# LVDS_repeater.net
KiCad netlist of a schematic drawn in Altium Designer
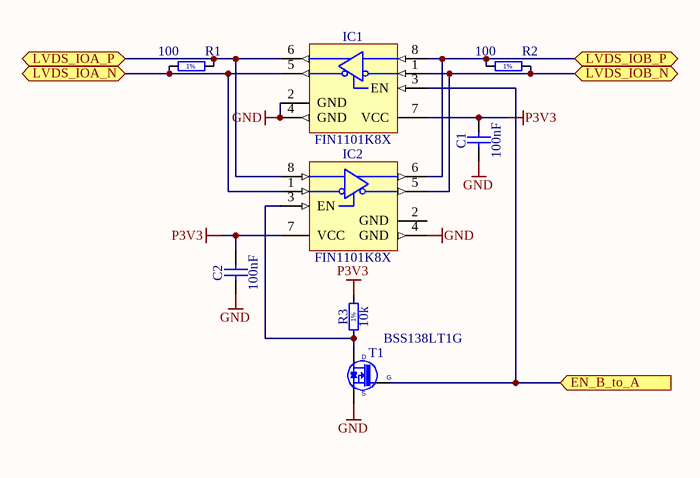
[diagram p0: LVDS_repeater.SchDoc]

(export (version "E")
  (design (tool "Eeschema 10.0.6"))
  (components
    (comp (ref "C1")
      (value "100nF")
      (footprint "CAPC1005X55N")
      (description "Non-polarised capacitor")
      (fields
        (field (name "PART NUMBER") "CC0402_100NF_16V_10%_X5R")
        (field (name "VOLTAGE") "16V")
        (field (name "AUTHOR") "CERN DEM JLC")
      )
      (libsource (lib "Capacitors") (part "Capacitor - non polarized"))
    )
    (comp (ref "C2")
      (value "100nF")
      (footprint "CAPC1005X55N")
      (description "Non-polarised capacitor")
      (fields
        (field (name "PART NUMBER") "CC0402_100NF_16V_10%_X5R")
        (field (name "VOLTAGE") "16V")
        (field (name "AUTHOR") "CERN DEM JLC")
      )
      (libsource (lib "Capacitors") (part "Capacitor - non polarized"))
    )
    (comp (ref "IC1")
      (value "FIN1101K8X")
      (footprint "SOP50P310X90-8N")
      (description "LVDS Single Port High Speed Repeater")
      (fields (field (name "MANUFACTURER") "FAIRCHILD SEMICONDUCTOR") (field (name "AUTHOR") "CERN DEM JLC"))
      (libsource (lib "ICs And Semiconductors") (part "FIN1101K8X"))
    )
    (comp (ref "IC2")
      (value "FIN1101K8X")
      (footprint "SOP50P310X90-8N")
      (description "LVDS Single Port High Speed Repeater")
      (fields (field (name "MANUFACTURER") "FAIRCHILD SEMICONDUCTOR") (field (name "AUTHOR") "CERN DEM JLC"))
      (libsource (lib "") (part "FIN1101K8X_1"))
    )
    (comp (ref "R1")
      (value "100")
      (footprint "RESC1005X40N")
      (description "Resistor - 1%")
      (fields
        (field (name "PART NUMBER") "R0402_100R_1%_0.1W_100PPM")
        (field (name "POWER") "0.1W")
        (field (name "AUTHOR") "CERN DEM JLC")
      )
      (libsource (lib "Resistors") (part "Resistor - 1%"))
    )
    (comp (ref "R2")
      (value "100")
      (footprint "RESC1005X40N")
      (description "Resistor - 1%")
      (fields
        (field (name "PART NUMBER") "R0402_100R_1%_0.1W_100PPM")
        (field (name "POWER") "0.1W")
        (field (name "AUTHOR") "CERN DEM JLC")
      )
      (libsource (lib "Resistors") (part "Resistor - 1%"))
    )
    (comp (ref "R3")
      (value "10k")
      (footprint "RESC1005X40N")
      (description "Resistor - 1%")
      (fields
        (field (name "PART NUMBER") "R0402_10K_1%_0.0625W_100PPM")
        (field (name "POWER") "0.0625W")
        (field (name "AUTHOR") "CERN DEM JLC")
      )
      (libsource (lib "Resistors") (part "Resistor - 1%"))
    )
    (comp (ref "T1")
      (value "BSS138LT1G")
      (footprint "SOT95P240X110-3N")
      (description "N-CHANNEL MOSFET WITH DIODE")
      (fields (field (name "MANUFACTURER") "ON SEMICONDUCTOR") (field (name "AUTHOR") "CERN DEM JLC"))
      (libsource (lib "ICs And Semiconductors") (part "N-MOSFET-D 1G 2S 3D"))
    )
  )
  (nets
    (net (code "1") (name "/EN_B_to_A") (class "Default")
      (node (ref "IC1") (pin "3") (pinfunction "EN_3") (pintype "input"))
      (node (ref "T1") (pin "1") (pinfunction "G_1") (pintype "passive"))
    )
    (net (code "2") (name "/LVDS_IOA_N") (class "Default")
      (node (ref "IC1") (pin "5") (pinfunction "DOUT-_5") (pintype "output"))
      (node (ref "IC2") (pin "1") (pinfunction "RIN-_1") (pintype "input"))
      (node (ref "R1") (pin "1") (pinfunction "1_1") (pintype "passive"))
    )
    (net (code "3") (name "/LVDS_IOA_P") (class "Default")
      (node (ref "IC1") (pin "6") (pinfunction "DOUT+_6") (pintype "output"))
      (node (ref "IC2") (pin "8") (pinfunction "RIN+_8") (pintype "input"))
      (node (ref "R1") (pin "2") (pinfunction "2_2") (pintype "passive"))
    )
    (net (code "4") (name "/LVDS_IOB_N") (class "Default")
      (node (ref "IC1") (pin "1") (pinfunction "RIN-_1") (pintype "input"))
      (node (ref "IC2") (pin "5") (pinfunction "DOUT-_5") (pintype "output"))
      (node (ref "R2") (pin "2") (pinfunction "2_2") (pintype "passive"))
    )
    (net (code "5") (name "/LVDS_IOB_P") (class "Default")
      (node (ref "IC1") (pin "8") (pinfunction "RIN+_8") (pintype "input"))
      (node (ref "IC2") (pin "6") (pinfunction "DOUT+_6") (pintype "output"))
      (node (ref "R2") (pin "1") (pinfunction "1_1") (pintype "passive"))
    )
    (net (code "6") (name "GND") (class "Default")
      (node (ref "C1") (pin "1") (pinfunction "1_1") (pintype "passive"))
      (node (ref "C2") (pin "1") (pinfunction "1_1") (pintype "passive"))
      (node (ref "IC1") (pin "2") (pinfunction "GND_2") (pintype "power_in"))
      (node (ref "IC1") (pin "4") (pinfunction "GND_4") (pintype "output"))
      (node (ref "IC2") (pin "4") (pinfunction "GND_4") (pintype "output"))
      (node (ref "T1") (pin "2") (pinfunction "S_2") (pintype "passive"))
    )
    (net (code "7") (name "Net-(IC2-EN)") (class "Default")
      (node (ref "IC2") (pin "3") (pinfunction "EN_3") (pintype "input"))
      (node (ref "R3") (pin "1") (pinfunction "1_1") (pintype "passive"))
      (node (ref "T1") (pin "3") (pinfunction "D_3") (pintype "passive"))
    )
    (net (code "8") (name "P3V3") (class "Default")
      (node (ref "C1") (pin "2") (pinfunction "2_2") (pintype "passive"))
      (node (ref "C2") (pin "2") (pinfunction "2_2") (pintype "passive"))
      (node (ref "IC1") (pin "7") (pinfunction "VCC_7") (pintype "power_in"))
      (node (ref "IC2") (pin "7") (pinfunction "VCC_7") (pintype "power_in"))
      (node (ref "R3") (pin "2") (pinfunction "2_2") (pintype "passive"))
    )
    (net (code "9") (name "unconnected-(IC2-GND-Pad2)") (class "Default")
      (node (ref "IC2") (pin "2") (pinfunction "GND_2") (pintype "power_in"))
    )
  )
)
